# SWDIsolator.net
KiCad netlist of a schematic drawn in EAGLE
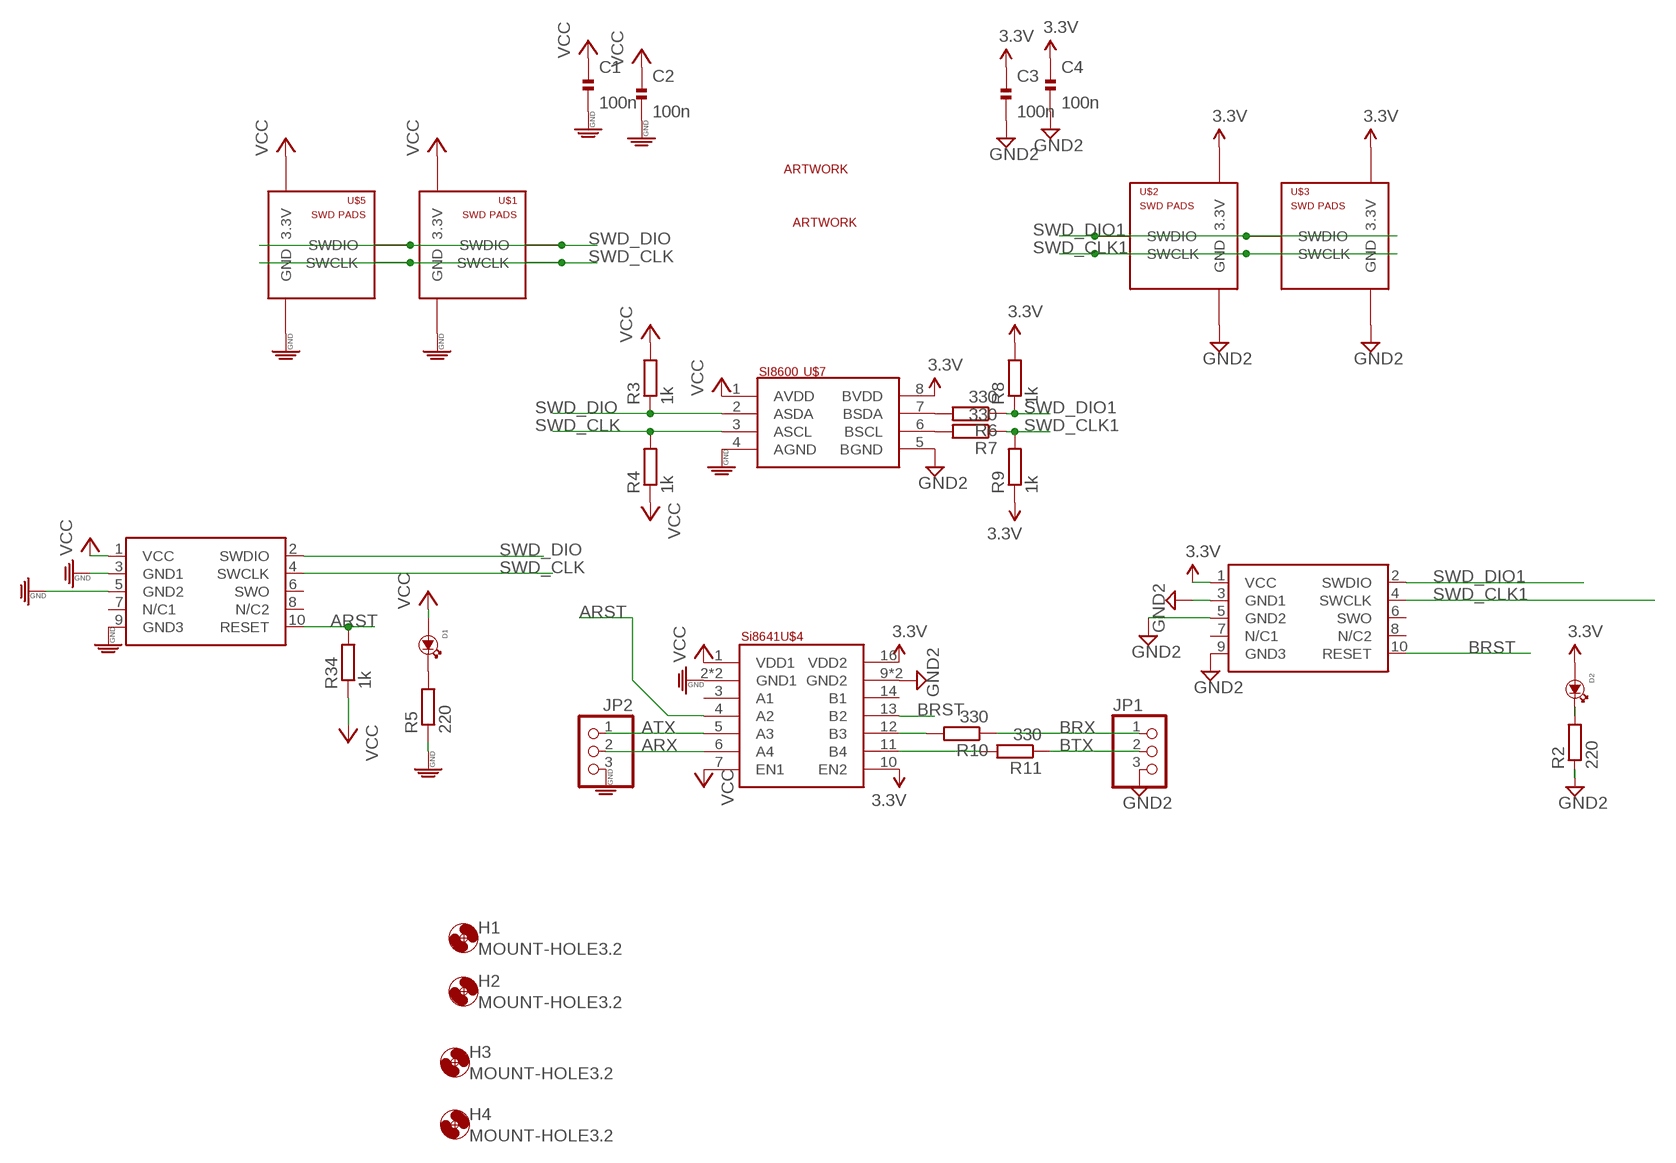
[diagram p0: schematic, sheet 1]

(export (version "E")
  (design (tool "Eeschema 10.0.6"))
  (components
    (comp (ref "C1")
      (value "100n")
      (footprint "eagle-import:C0402")
      (libsource (lib "eagle-import") (part "C-EUC0402"))
    )
    (comp (ref "C2")
      (value "100n")
      (footprint "eagle-import:C0402")
      (libsource (lib "eagle-import") (part "C-EUC0402"))
    )
    (comp (ref "C3")
      (value "100n")
      (footprint "eagle-import:C0402")
      (libsource (lib "eagle-import") (part "C-EUC0402"))
    )
    (comp (ref "C4")
      (value "100n")
      (footprint "eagle-import:C0402")
      (libsource (lib "eagle-import") (part "C-EUC0402"))
    )
    (comp (ref "D1")
      (value "LED")
      (footprint "eagle-import:LED0603")
      (libsource (lib "eagle-import") (part "LED"))
    )
    (comp (ref "D2")
      (value "LED")
      (footprint "eagle-import:LED0603")
      (libsource (lib "eagle-import") (part "LED"))
    )
    (comp (ref "H1")
      (value "MOUNT-HOLE3.2")
      (footprint "eagle-import:3,2")
      (libsource (lib "eagle-import") (part "MOUNT-HOLE3.2"))
    )
    (comp (ref "H2")
      (value "MOUNT-HOLE3.2")
      (footprint "eagle-import:3,2")
      (libsource (lib "eagle-import") (part "MOUNT-HOLE3.2"))
    )
    (comp (ref "H3")
      (value "MOUNT-HOLE3.2")
      (footprint "eagle-import:3,2")
      (libsource (lib "eagle-import") (part "MOUNT-HOLE3.2"))
    )
    (comp (ref "H4")
      (value "MOUNT-HOLE3.2")
      (footprint "eagle-import:3,2")
      (libsource (lib "eagle-import") (part "MOUNT-HOLE3.2"))
    )
    (comp (ref "JP1")
      (value "PINHD-1X3CB")
      (footprint "eagle-import:1X03-CLEANBIG")
      (libsource (lib "eagle-import") (part "PINHD-1X3CB"))
    )
    (comp (ref "JP2")
      (value "PINHD-1X3CB")
      (footprint "eagle-import:1X03-CLEANBIG")
      (libsource (lib "eagle-import") (part "PINHD-1X3CB"))
    )
    (comp (ref "R2")
      (value "220")
      (footprint "eagle-import:R0402")
      (libsource (lib "eagle-import") (part "R-EU_R0402"))
    )
    (comp (ref "R3")
      (value "1k")
      (footprint "eagle-import:R0402")
      (libsource (lib "eagle-import") (part "R-EU_R0402"))
    )
    (comp (ref "R4")
      (value "1k")
      (footprint "eagle-import:R0402")
      (libsource (lib "eagle-import") (part "R-EU_R0402"))
    )
    (comp (ref "R5")
      (value "220")
      (footprint "eagle-import:R0402")
      (libsource (lib "eagle-import") (part "R-EU_R0402"))
    )
    (comp (ref "R6")
      (value "330")
      (footprint "eagle-import:R0402")
      (libsource (lib "eagle-import") (part "R-EU_R0402"))
    )
    (comp (ref "R7")
      (value "330")
      (footprint "eagle-import:R0402")
      (libsource (lib "eagle-import") (part "R-EU_R0402"))
    )
    (comp (ref "R8")
      (value "1k")
      (footprint "eagle-import:R0402")
      (libsource (lib "eagle-import") (part "R-EU_R0402"))
    )
    (comp (ref "R9")
      (value "1k")
      (footprint "eagle-import:R0402")
      (libsource (lib "eagle-import") (part "R-EU_R0402"))
    )
    (comp (ref "R10")
      (value "330")
      (footprint "eagle-import:R0402")
      (libsource (lib "eagle-import") (part "R-EU_R0402"))
    )
    (comp (ref "R11")
      (value "330")
      (footprint "eagle-import:R0402")
      (libsource (lib "eagle-import") (part "R-EU_R0402"))
    )
    (comp (ref "R34")
      (value "1k")
      (footprint "eagle-import:R0402")
      (libsource (lib "eagle-import") (part "R-EU_R0402"))
    )
    (comp (ref "SWD1")
      (value "CORTEX_SWD")
      (footprint "eagle-import:M50-3600542")
      (libsource (lib "eagle-import") (part "CORTEX_SWD"))
    )
    (comp (ref "SWD2")
      (value "CORTEX_SWD")
      (footprint "eagle-import:M50-3600542")
      (libsource (lib "eagle-import") (part "CORTEX_SWD"))
    )
    (comp (ref "U$1")
      (value "SWD_PADS")
      (footprint "eagle-import:SWDPADS")
      (libsource (lib "eagle-import") (part "SWD_PADS"))
    )
    (comp (ref "U$2")
      (value "SWD_PADS")
      (footprint "eagle-import:SWDPADS")
      (libsource (lib "eagle-import") (part "SWD_PADS"))
    )
    (comp (ref "U$3")
      (value "SWD_PADS_NOTITLE")
      (footprint "eagle-import:SWDPADS_NOTITLE")
      (libsource (lib "eagle-import") (part "SWD_PADS_NOTITLE"))
    )
    (comp (ref "U$4")
      (value "SI8641")
      (footprint "eagle-import:SO16")
      (libsource (lib "eagle-import") (part "SI8641"))
    )
    (comp (ref "U$5")
      (value "SWD_PADS_NOTITLE")
      (footprint "eagle-import:SWDPADS_NOTITLE")
      (libsource (lib "eagle-import") (part "SWD_PADS_NOTITLE"))
    )
    (comp (ref "U$6")
      (value "TINRS_ARTWORKLOGO")
      (footprint "eagle-import:TINRSLOGO")
      (libsource (lib "eagle-import") (part "TINRS_ARTWORKLOGO"))
    )
    (comp (ref "U$7")
      (value "SI8600AB")
      (footprint "eagle-import:SO8")
      (libsource (lib "eagle-import") (part "SI8600"))
    )
    (comp (ref "U$8")
      (value "TINRS_ARTWORKROCKET")
      (footprint "eagle-import:TINRS_ROCKET")
      (libsource (lib "eagle-import") (part "TINRS_ARTWORKROCKET"))
    )
  )
  (nets
    (net (code "1") (name "/ARST") (class "Default")
      (node (ref "R34") (pin "2") (pinfunction "2_2") (pintype "passive"))
      (node (ref "SWD1") (pin "10") (pinfunction "RESET_10") (pintype "bidirectional"))
      (node (ref "U$4") (pin "4") (pinfunction "A2_4") (pintype "bidirectional"))
    )
    (net (code "2") (name "/ARX") (class "Default")
      (node (ref "JP2") (pin "2") (pinfunction "2_2") (pintype "passive"))
      (node (ref "U$4") (pin "6") (pinfunction "A4_6") (pintype "bidirectional"))
    )
    (net (code "3") (name "/ATX") (class "Default")
      (node (ref "JP2") (pin "1") (pinfunction "1_1") (pintype "passive"))
      (node (ref "U$4") (pin "5") (pinfunction "A3_5") (pintype "bidirectional"))
    )
    (net (code "4") (name "/BRST") (class "Default")
      (node (ref "SWD2") (pin "10") (pinfunction "RESET_10") (pintype "bidirectional"))
      (node (ref "U$4") (pin "13") (pinfunction "B2_13") (pintype "bidirectional"))
    )
    (net (code "5") (name "/BRX") (class "Default")
      (node (ref "JP1") (pin "1") (pinfunction "1_1") (pintype "passive"))
      (node (ref "R10") (pin "1") (pinfunction "1_1") (pintype "passive"))
    )
    (net (code "6") (name "/BTX") (class "Default")
      (node (ref "JP1") (pin "2") (pinfunction "2_2") (pintype "passive"))
      (node (ref "R11") (pin "1") (pinfunction "1_1") (pintype "passive"))
    )
    (net (code "7") (name "/SWD_CLK") (class "Default")
      (node (ref "R4") (pin "2") (pinfunction "2_2") (pintype "passive"))
      (node (ref "SWD1") (pin "4") (pinfunction "SWCLK_4") (pintype "bidirectional"))
      (node (ref "U$1") (pin "SWCLK") (pinfunction "SWCLK_SWCLK") (pintype "bidirectional"))
      (node (ref "U$5") (pin "SWCLK") (pinfunction "SWCLK_SWCLK") (pintype "bidirectional"))
      (node (ref "U$7") (pin "3") (pinfunction "ASCL_3") (pintype "bidirectional"))
    )
    (net (code "8") (name "/SWD_CLK1") (class "Default")
      (node (ref "R7") (pin "1") (pinfunction "1_1") (pintype "passive"))
      (node (ref "R9") (pin "2") (pinfunction "2_2") (pintype "passive"))
      (node (ref "SWD2") (pin "4") (pinfunction "SWCLK_4") (pintype "bidirectional"))
      (node (ref "U$2") (pin "SWCLK") (pinfunction "SWCLK_SWCLK") (pintype "bidirectional"))
      (node (ref "U$3") (pin "SWCLK") (pinfunction "SWCLK_SWCLK") (pintype "bidirectional"))
    )
    (net (code "9") (name "/SWD_DIO") (class "Default")
      (node (ref "R3") (pin "1") (pinfunction "1_1") (pintype "passive"))
      (node (ref "SWD1") (pin "2") (pinfunction "SWDIO_2") (pintype "bidirectional"))
      (node (ref "U$1") (pin "SWDIO") (pinfunction "SWDIO_SWDIO") (pintype "bidirectional"))
      (node (ref "U$5") (pin "SWDIO") (pinfunction "SWDIO_SWDIO") (pintype "bidirectional"))
      (node (ref "U$7") (pin "2") (pinfunction "ASDA_2") (pintype "bidirectional"))
    )
    (net (code "10") (name "/SWD_DIO1") (class "Default")
      (node (ref "R6") (pin "1") (pinfunction "1_1") (pintype "passive"))
      (node (ref "R8") (pin "1") (pinfunction "1_1") (pintype "passive"))
      (node (ref "SWD2") (pin "2") (pinfunction "SWDIO_2") (pintype "bidirectional"))
      (node (ref "U$2") (pin "SWDIO") (pinfunction "SWDIO_SWDIO") (pintype "bidirectional"))
      (node (ref "U$3") (pin "SWDIO") (pinfunction "SWDIO_SWDIO") (pintype "bidirectional"))
    )
    (net (code "11") (name "3.3V") (class "Default")
      (node (ref "C3") (pin "1") (pinfunction "1_1") (pintype "passive"))
      (node (ref "C4") (pin "1") (pinfunction "1_1") (pintype "passive"))
      (node (ref "D2") (pin "+") (pinfunction "+_+") (pintype "passive"))
      (node (ref "R8") (pin "2") (pinfunction "2_2") (pintype "passive"))
      (node (ref "R9") (pin "1") (pinfunction "1_1") (pintype "passive"))
      (node (ref "SWD2") (pin "1") (pinfunction "VCC_1") (pintype "bidirectional"))
      (node (ref "U$2") (pin "3.3V") (pinfunction "3.3V_3.3V") (pintype "bidirectional"))
      (node (ref "U$3") (pin "3.3V") (pinfunction "3.3V_3.3V") (pintype "bidirectional"))
      (node (ref "U$4") (pin "10") (pinfunction "EN2_10") (pintype "bidirectional"))
      (node (ref "U$4") (pin "16") (pinfunction "VDD2_16") (pintype "bidirectional"))
      (node (ref "U$7") (pin "8") (pinfunction "BVDD_8") (pintype "bidirectional"))
    )
    (net (code "12") (name "GND") (class "Default")
      (node (ref "C1") (pin "2") (pinfunction "2_2") (pintype "passive"))
      (node (ref "C2") (pin "2") (pinfunction "2_2") (pintype "passive"))
      (node (ref "JP2") (pin "3") (pinfunction "3_3") (pintype "passive"))
      (node (ref "R5") (pin "1") (pinfunction "1_1") (pintype "passive"))
      (node (ref "SWD1") (pin "3") (pinfunction "GND1_3") (pintype "bidirectional"))
      (node (ref "SWD1") (pin "5") (pinfunction "GND2_5") (pintype "bidirectional"))
      (node (ref "SWD1") (pin "9") (pinfunction "GND3_9") (pintype "bidirectional"))
      (node (ref "U$1") (pin "GND") (pinfunction "GND_GND") (pintype "bidirectional"))
      (node (ref "U$4") (pin "2") (pinfunction "GND1_2") (pintype "bidirectional"))
      (node (ref "U$4") (pin "8") (pinfunction "GND1_8") (pintype "bidirectional"))
      (node (ref "U$5") (pin "GND") (pinfunction "GND_GND") (pintype "bidirectional"))
      (node (ref "U$7") (pin "4") (pinfunction "AGND_4") (pintype "bidirectional"))
    )
    (net (code "13") (name "GND2") (class "Default")
      (node (ref "C3") (pin "2") (pinfunction "2_2") (pintype "passive"))
      (node (ref "C4") (pin "2") (pinfunction "2_2") (pintype "passive"))
      (node (ref "JP1") (pin "3") (pinfunction "3_3") (pintype "passive"))
      (node (ref "R2") (pin "1") (pinfunction "1_1") (pintype "passive"))
      (node (ref "SWD2") (pin "3") (pinfunction "GND1_3") (pintype "bidirectional"))
      (node (ref "SWD2") (pin "5") (pinfunction "GND2_5") (pintype "bidirectional"))
      (node (ref "SWD2") (pin "9") (pinfunction "GND3_9") (pintype "bidirectional"))
      (node (ref "U$2") (pin "GND") (pinfunction "GND_GND") (pintype "bidirectional"))
      (node (ref "U$3") (pin "GND") (pinfunction "GND_GND") (pintype "bidirectional"))
      (node (ref "U$4") (pin "15") (pinfunction "GND2_15") (pintype "bidirectional"))
      (node (ref "U$4") (pin "9") (pinfunction "GND2_9") (pintype "bidirectional"))
      (node (ref "U$7") (pin "5") (pinfunction "BGND_5") (pintype "bidirectional"))
    )
    (net (code "14") (name "Net-(D1-Pad-)") (class "Default")
      (node (ref "D1") (pin "-") (pinfunction "-_-") (pintype "passive"))
      (node (ref "R5") (pin "2") (pinfunction "2_2") (pintype "passive"))
    )
    (net (code "15") (name "Net-(D2-Pad-)") (class "Default")
      (node (ref "D2") (pin "-") (pinfunction "-_-") (pintype "passive"))
      (node (ref "R2") (pin "2") (pinfunction "2_2") (pintype "passive"))
    )
    (net (code "16") (name "Net-(U$4-B3)") (class "Default")
      (node (ref "R10") (pin "2") (pinfunction "2_2") (pintype "passive"))
      (node (ref "U$4") (pin "12") (pinfunction "B3_12") (pintype "bidirectional"))
    )
    (net (code "17") (name "Net-(U$4-B4)") (class "Default")
      (node (ref "R11") (pin "2") (pinfunction "2_2") (pintype "passive"))
      (node (ref "U$4") (pin "11") (pinfunction "B4_11") (pintype "bidirectional"))
    )
    (net (code "18") (name "Net-(U$7-BSCL)") (class "Default")
      (node (ref "R7") (pin "2") (pinfunction "2_2") (pintype "passive"))
      (node (ref "U$7") (pin "6") (pinfunction "BSCL_6") (pintype "bidirectional"))
    )
    (net (code "19") (name "Net-(U$7-BSDA)") (class "Default")
      (node (ref "R6") (pin "2") (pinfunction "2_2") (pintype "passive"))
      (node (ref "U$7") (pin "7") (pinfunction "BSDA_7") (pintype "bidirectional"))
    )
    (net (code "20") (name "VCC") (class "Default")
      (node (ref "C1") (pin "1") (pinfunction "1_1") (pintype "passive"))
      (node (ref "C2") (pin "1") (pinfunction "1_1") (pintype "passive"))
      (node (ref "D1") (pin "+") (pinfunction "+_+") (pintype "passive"))
      (node (ref "R3") (pin "2") (pinfunction "2_2") (pintype "passive"))
      (node (ref "R34") (pin "1") (pinfunction "1_1") (pintype "passive"))
      (node (ref "R4") (pin "1") (pinfunction "1_1") (pintype "passive"))
      (node (ref "SWD1") (pin "1") (pinfunction "VCC_1") (pintype "bidirectional"))
      (node (ref "U$1") (pin "3.3V") (pinfunction "3.3V_3.3V") (pintype "bidirectional"))
      (node (ref "U$4") (pin "1") (pinfunction "VDD1_1") (pintype "bidirectional"))
      (node (ref "U$4") (pin "7") (pinfunction "EN1_7") (pintype "bidirectional"))
      (node (ref "U$5") (pin "3.3V") (pinfunction "3.3V_3.3V") (pintype "bidirectional"))
      (node (ref "U$7") (pin "1") (pinfunction "AVDD_1") (pintype "bidirectional"))
    )
    (net (code "21") (name "unconnected-(SWD1-N{slash}C1-Pad7)") (class "Default")
      (node (ref "SWD1") (pin "7") (pinfunction "N/C1_7") (pintype "bidirectional"))
    )
    (net (code "22") (name "unconnected-(SWD1-N{slash}C2-Pad8)") (class "Default")
      (node (ref "SWD1") (pin "8") (pinfunction "N/C2_8") (pintype "bidirectional"))
    )
    (net (code "23") (name "unconnected-(SWD1-SWO-Pad6)") (class "Default")
      (node (ref "SWD1") (pin "6") (pinfunction "SWO_6") (pintype "bidirectional"))
    )
    (net (code "24") (name "unconnected-(SWD2-N{slash}C1-Pad7)") (class "Default")
      (node (ref "SWD2") (pin "7") (pinfunction "N/C1_7") (pintype "bidirectional"))
    )
    (net (code "25") (name "unconnected-(SWD2-N{slash}C2-Pad8)") (class "Default")
      (node (ref "SWD2") (pin "8") (pinfunction "N/C2_8") (pintype "bidirectional"))
    )
    (net (code "26") (name "unconnected-(SWD2-SWO-Pad6)") (class "Default")
      (node (ref "SWD2") (pin "6") (pinfunction "SWO_6") (pintype "bidirectional"))
    )
    (net (code "27") (name "unconnected-(U$4-A1-Pad3)") (class "Default")
      (node (ref "U$4") (pin "3") (pinfunction "A1_3") (pintype "bidirectional"))
    )
    (net (code "28") (name "unconnected-(U$4-B1-Pad14)") (class "Default")
      (node (ref "U$4") (pin "14") (pinfunction "B1_14") (pintype "bidirectional"))
    )
  )
)
